# ADC_Buffers.net
KiCad netlist of a schematic drawn in Altium Designer
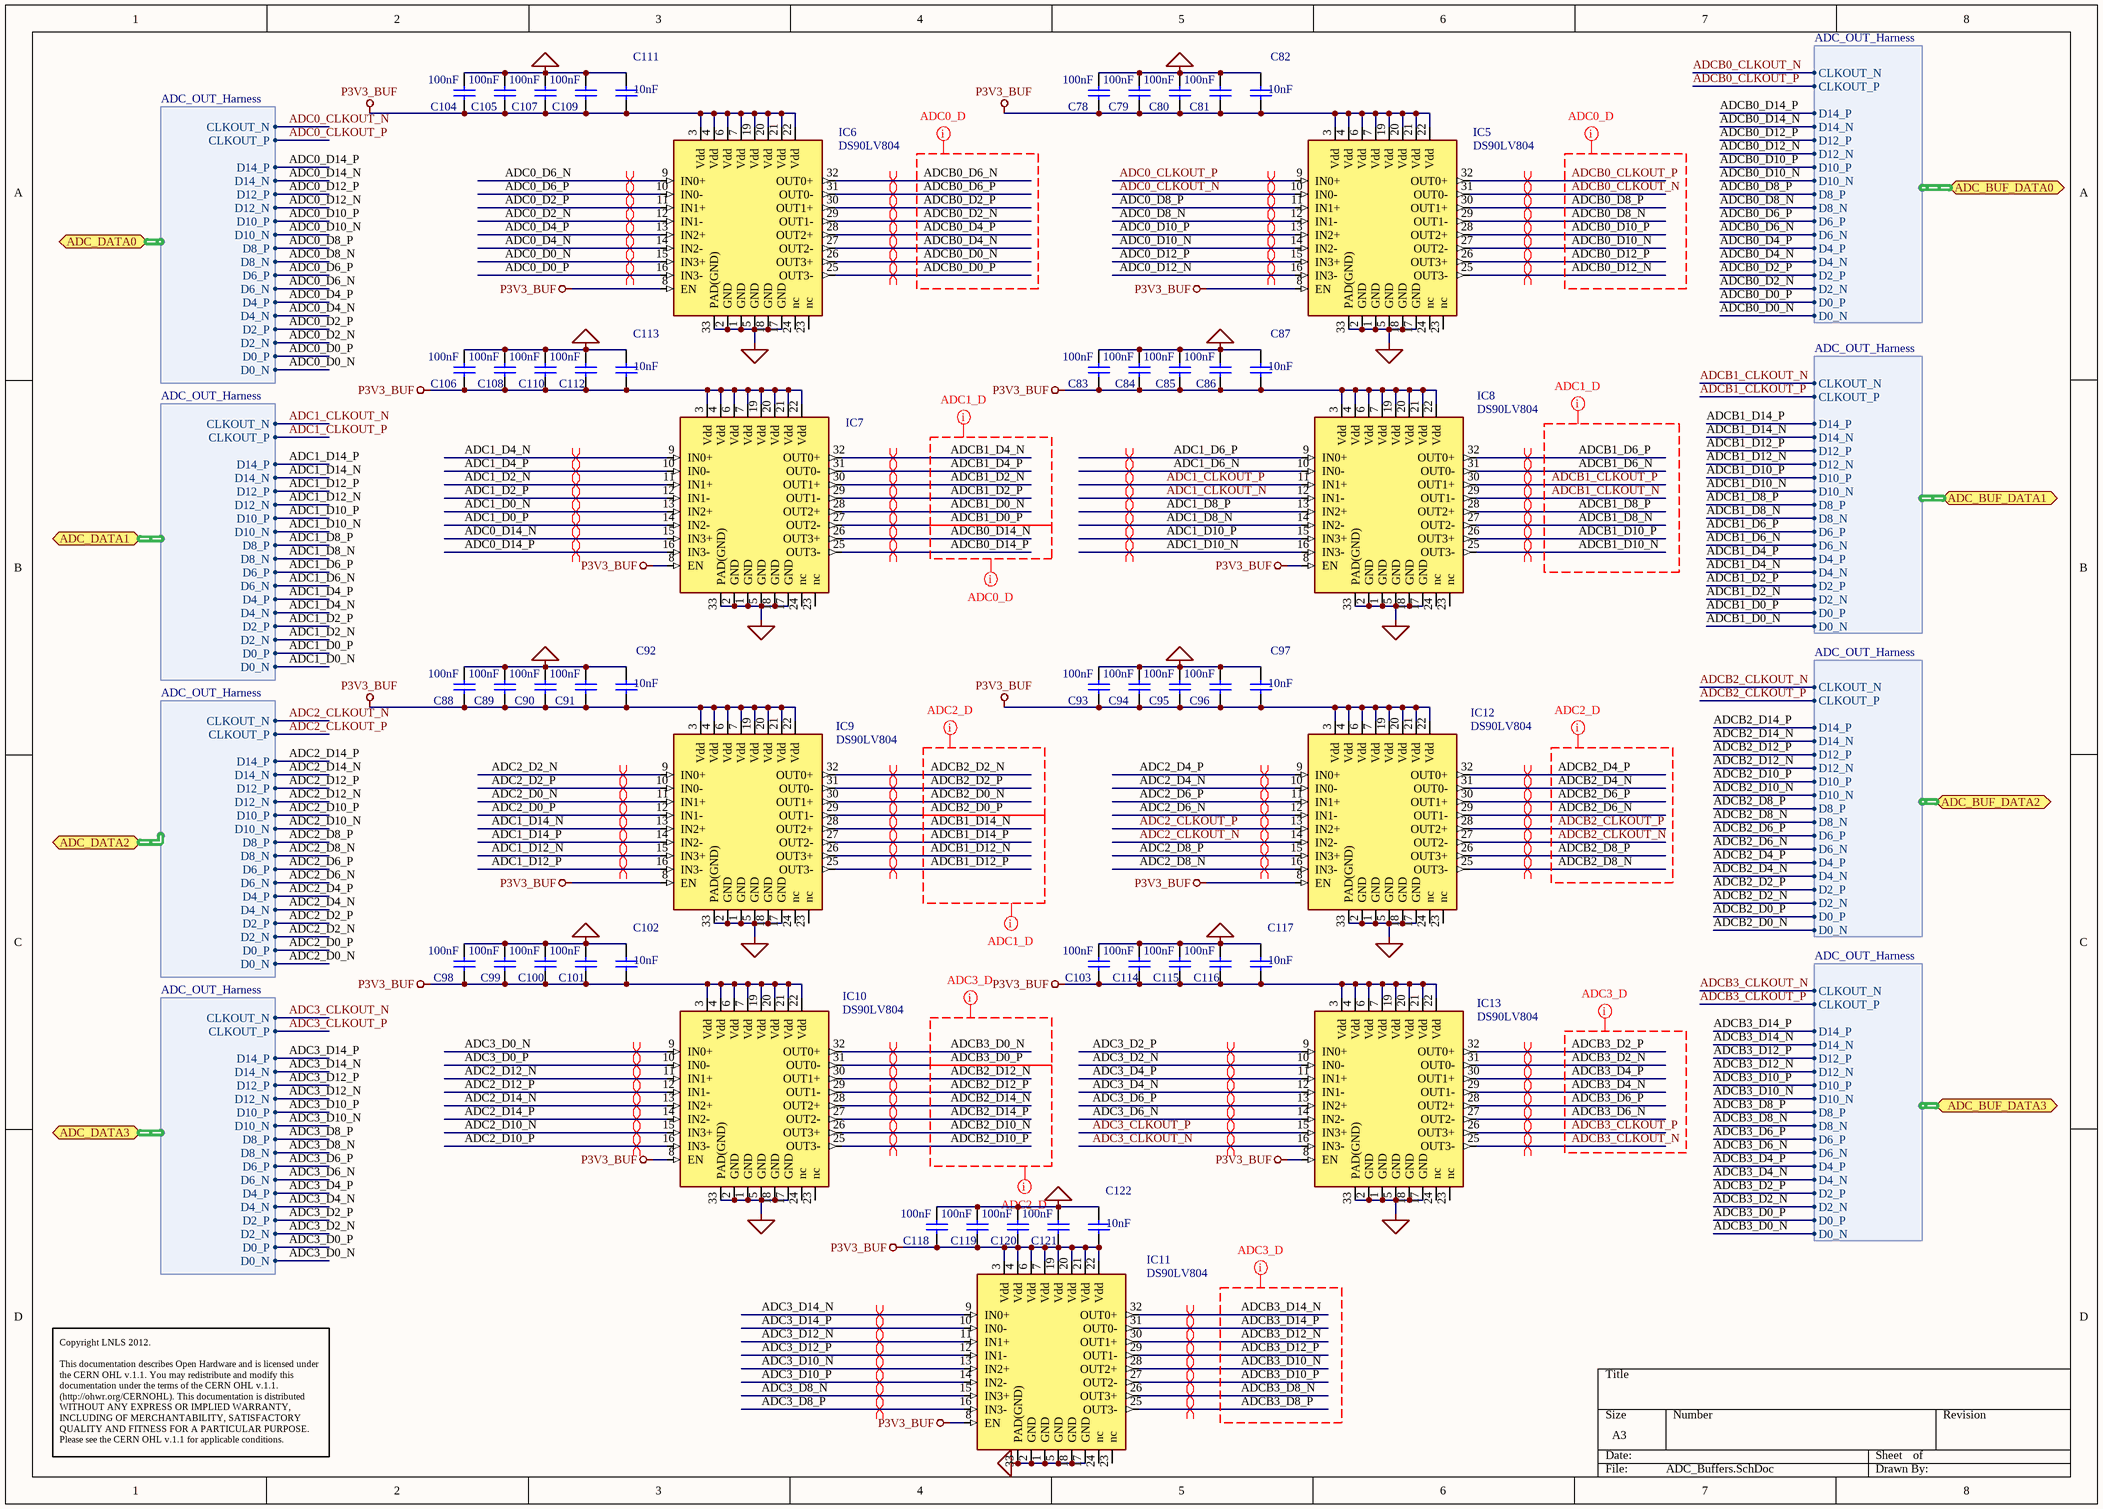
[diagram p0: ADC_Buffers.SchDoc]

(export (version "E")
  (design (tool "Eeschema 10.0.6"))
  (components
    (comp (ref "C78")
      (value "100nF")
      (footprint "CAPC0603X33N")
      (description "Non-polarised capacitor")
      (fields
        (field (name "PART NUMBER") "CC0201_100NF_6.3V_10%_X5R")
        (field (name "VOLTAGE") "6.3V")
        (field (name "AUTHOR") "CERN DEM JLC")
      )
      (libsource (lib "Capacitors") (part "Capacitor - non polarized"))
    )
    (comp (ref "C79")
      (value "100nF")
      (footprint "CAPC0603X33N")
      (description "Non-polarised capacitor")
      (fields
        (field (name "PART NUMBER") "CC0201_100NF_6.3V_10%_X5R")
        (field (name "VOLTAGE") "6.3V")
        (field (name "AUTHOR") "CERN DEM JLC")
      )
      (libsource (lib "Capacitors") (part "Capacitor - non polarized"))
    )
    (comp (ref "C80")
      (value "100nF")
      (footprint "CAPC0603X33N")
      (description "Non-polarised capacitor")
      (fields
        (field (name "PART NUMBER") "CC0201_100NF_6.3V_10%_X5R")
        (field (name "VOLTAGE") "6.3V")
        (field (name "AUTHOR") "CERN DEM JLC")
      )
      (libsource (lib "Capacitors") (part "Capacitor - non polarized"))
    )
    (comp (ref "C81")
      (value "100nF")
      (footprint "CAPC0603X33N")
      (description "Non-polarised capacitor")
      (fields
        (field (name "PART NUMBER") "CC0201_100NF_6.3V_10%_X5R")
        (field (name "VOLTAGE") "6.3V")
        (field (name "AUTHOR") "CERN DEM JLC")
      )
      (libsource (lib "Capacitors") (part "Capacitor - non polarized"))
    )
    (comp (ref "C82")
      (value "10nF")
      (footprint "CAPC0603X33N")
      (description "Non-polarised capacitor")
      (fields
        (field (name "PART NUMBER") "CC0201_10NF_10V_10%_X7R")
        (field (name "VOLTAGE") "10V")
        (field (name "AUTHOR") "LNLS DIG GBMB")
      )
      (libsource (lib "Capacitors") (part "Capacitor - non polarized"))
    )
    (comp (ref "C83")
      (value "100nF")
      (footprint "CAPC0603X33N")
      (description "Non-polarised capacitor")
      (fields
        (field (name "PART NUMBER") "CC0201_100NF_6.3V_10%_X5R")
        (field (name "VOLTAGE") "6.3V")
        (field (name "AUTHOR") "CERN DEM JLC")
      )
      (libsource (lib "Capacitors") (part "Capacitor - non polarized"))
    )
    (comp (ref "C84")
      (value "100nF")
      (footprint "CAPC0603X33N")
      (description "Non-polarised capacitor")
      (fields
        (field (name "PART NUMBER") "CC0201_100NF_6.3V_10%_X5R")
        (field (name "VOLTAGE") "6.3V")
        (field (name "AUTHOR") "CERN DEM JLC")
      )
      (libsource (lib "Capacitors") (part "Capacitor - non polarized"))
    )
    (comp (ref "C85")
      (value "100nF")
      (footprint "CAPC0603X33N")
      (description "Non-polarised capacitor")
      (fields
        (field (name "PART NUMBER") "CC0201_100NF_6.3V_10%_X5R")
        (field (name "VOLTAGE") "6.3V")
        (field (name "AUTHOR") "CERN DEM JLC")
      )
      (libsource (lib "Capacitors") (part "Capacitor - non polarized"))
    )
    (comp (ref "C86")
      (value "100nF")
      (footprint "CAPC0603X33N")
      (description "Non-polarised capacitor")
      (fields
        (field (name "PART NUMBER") "CC0201_100NF_6.3V_10%_X5R")
        (field (name "VOLTAGE") "6.3V")
        (field (name "AUTHOR") "CERN DEM JLC")
      )
      (libsource (lib "Capacitors") (part "Capacitor - non polarized"))
    )
    (comp (ref "C87")
      (value "10nF")
      (footprint "CAPC0603X33N")
      (description "Non-polarised capacitor")
      (fields
        (field (name "PART NUMBER") "CC0201_10NF_10V_10%_X7R")
        (field (name "VOLTAGE") "10V")
        (field (name "AUTHOR") "LNLS DIG GBMB")
      )
      (libsource (lib "Capacitors") (part "Capacitor - non polarized"))
    )
    (comp (ref "C88")
      (value "100nF")
      (footprint "CAPC0603X33N")
      (description "Non-polarised capacitor")
      (fields
        (field (name "PART NUMBER") "CC0201_100NF_6.3V_10%_X5R")
        (field (name "VOLTAGE") "6.3V")
        (field (name "AUTHOR") "CERN DEM JLC")
      )
      (libsource (lib "Capacitors") (part "Capacitor - non polarized"))
    )
    (comp (ref "C89")
      (value "100nF")
      (footprint "CAPC0603X33N")
      (description "Non-polarised capacitor")
      (fields
        (field (name "PART NUMBER") "CC0201_100NF_6.3V_10%_X5R")
        (field (name "VOLTAGE") "6.3V")
        (field (name "AUTHOR") "CERN DEM JLC")
      )
      (libsource (lib "Capacitors") (part "Capacitor - non polarized"))
    )
    (comp (ref "C90")
      (value "100nF")
      (footprint "CAPC0603X33N")
      (description "Non-polarised capacitor")
      (fields
        (field (name "PART NUMBER") "CC0201_100NF_6.3V_10%_X5R")
        (field (name "VOLTAGE") "6.3V")
        (field (name "AUTHOR") "CERN DEM JLC")
      )
      (libsource (lib "Capacitors") (part "Capacitor - non polarized"))
    )
    (comp (ref "C91")
      (value "100nF")
      (footprint "CAPC0603X33N")
      (description "Non-polarised capacitor")
      (fields
        (field (name "PART NUMBER") "CC0201_100NF_6.3V_10%_X5R")
        (field (name "VOLTAGE") "6.3V")
        (field (name "AUTHOR") "CERN DEM JLC")
      )
      (libsource (lib "Capacitors") (part "Capacitor - non polarized"))
    )
    (comp (ref "C92")
      (value "10nF")
      (footprint "CAPC0603X33N")
      (description "Non-polarised capacitor")
      (fields
        (field (name "PART NUMBER") "CC0201_10NF_10V_10%_X7R")
        (field (name "VOLTAGE") "10V")
        (field (name "AUTHOR") "LNLS DIG GBMB")
      )
      (libsource (lib "Capacitors") (part "Capacitor - non polarized"))
    )
    (comp (ref "C93")
      (value "100nF")
      (footprint "CAPC0603X33N")
      (description "Non-polarised capacitor")
      (fields
        (field (name "PART NUMBER") "CC0201_100NF_6.3V_10%_X5R")
        (field (name "VOLTAGE") "6.3V")
        (field (name "AUTHOR") "CERN DEM JLC")
      )
      (libsource (lib "Capacitors") (part "Capacitor - non polarized"))
    )
    (comp (ref "C94")
      (value "100nF")
      (footprint "CAPC0603X33N")
      (description "Non-polarised capacitor")
      (fields
        (field (name "PART NUMBER") "CC0201_100NF_6.3V_10%_X5R")
        (field (name "VOLTAGE") "6.3V")
        (field (name "AUTHOR") "CERN DEM JLC")
      )
      (libsource (lib "Capacitors") (part "Capacitor - non polarized"))
    )
    (comp (ref "C95")
      (value "100nF")
      (footprint "CAPC0603X33N")
      (description "Non-polarised capacitor")
      (fields
        (field (name "PART NUMBER") "CC0201_100NF_6.3V_10%_X5R")
        (field (name "VOLTAGE") "6.3V")
        (field (name "AUTHOR") "CERN DEM JLC")
      )
      (libsource (lib "Capacitors") (part "Capacitor - non polarized"))
    )
    (comp (ref "C96")
      (value "100nF")
      (footprint "CAPC0603X33N")
      (description "Non-polarised capacitor")
      (fields
        (field (name "PART NUMBER") "CC0201_100NF_6.3V_10%_X5R")
        (field (name "VOLTAGE") "6.3V")
        (field (name "AUTHOR") "CERN DEM JLC")
      )
      (libsource (lib "Capacitors") (part "Capacitor - non polarized"))
    )
    (comp (ref "C97")
      (value "10nF")
      (footprint "CAPC0603X33N")
      (description "Non-polarised capacitor")
      (fields
        (field (name "PART NUMBER") "CC0201_10NF_10V_10%_X7R")
        (field (name "VOLTAGE") "10V")
        (field (name "AUTHOR") "LNLS DIG GBMB")
      )
      (libsource (lib "Capacitors") (part "Capacitor - non polarized"))
    )
    (comp (ref "C98")
      (value "100nF")
      (footprint "CAPC0603X33N")
      (description "Non-polarised capacitor")
      (fields
        (field (name "PART NUMBER") "CC0201_100NF_6.3V_10%_X5R")
        (field (name "VOLTAGE") "6.3V")
        (field (name "AUTHOR") "CERN DEM JLC")
      )
      (libsource (lib "Capacitors") (part "Capacitor - non polarized"))
    )
    (comp (ref "C99")
      (value "100nF")
      (footprint "CAPC0603X33N")
      (description "Non-polarised capacitor")
      (fields
        (field (name "PART NUMBER") "CC0201_100NF_6.3V_10%_X5R")
        (field (name "VOLTAGE") "6.3V")
        (field (name "AUTHOR") "CERN DEM JLC")
      )
      (libsource (lib "Capacitors") (part "Capacitor - non polarized"))
    )
    (comp (ref "C100")
      (value "100nF")
      (footprint "CAPC0603X33N")
      (description "Non-polarised capacitor")
      (fields
        (field (name "PART NUMBER") "CC0201_100NF_6.3V_10%_X5R")
        (field (name "VOLTAGE") "6.3V")
        (field (name "AUTHOR") "CERN DEM JLC")
      )
      (libsource (lib "Capacitors") (part "Capacitor - non polarized"))
    )
    (comp (ref "C101")
      (value "100nF")
      (footprint "CAPC0603X33N")
      (description "Non-polarised capacitor")
      (fields
        (field (name "PART NUMBER") "CC0201_100NF_6.3V_10%_X5R")
        (field (name "VOLTAGE") "6.3V")
        (field (name "AUTHOR") "CERN DEM JLC")
      )
      (libsource (lib "Capacitors") (part "Capacitor - non polarized"))
    )
    (comp (ref "C102")
      (value "10nF")
      (footprint "CAPC0603X33N")
      (description "Non-polarised capacitor")
      (fields
        (field (name "PART NUMBER") "CC0201_10NF_10V_10%_X7R")
        (field (name "VOLTAGE") "10V")
        (field (name "AUTHOR") "LNLS DIG GBMB")
      )
      (libsource (lib "Capacitors") (part "Capacitor - non polarized"))
    )
    (comp (ref "C103")
      (value "100nF")
      (footprint "CAPC0603X33N")
      (description "Non-polarised capacitor")
      (fields
        (field (name "PART NUMBER") "CC0201_100NF_6.3V_10%_X5R")
        (field (name "VOLTAGE") "6.3V")
        (field (name "AUTHOR") "CERN DEM JLC")
      )
      (libsource (lib "Capacitors") (part "Capacitor - non polarized"))
    )
    (comp (ref "C104")
      (value "100nF")
      (footprint "CAPC0603X33N")
      (description "Non-polarised capacitor")
      (fields
        (field (name "PART NUMBER") "CC0201_100NF_6.3V_10%_X5R")
        (field (name "VOLTAGE") "6.3V")
        (field (name "AUTHOR") "CERN DEM JLC")
      )
      (libsource (lib "Capacitors") (part "Capacitor - non polarized"))
    )
    (comp (ref "C105")
      (value "100nF")
      (footprint "CAPC0603X33N")
      (description "Non-polarised capacitor")
      (fields
        (field (name "PART NUMBER") "CC0201_100NF_6.3V_10%_X5R")
        (field (name "VOLTAGE") "6.3V")
        (field (name "AUTHOR") "CERN DEM JLC")
      )
      (libsource (lib "Capacitors") (part "Capacitor - non polarized"))
    )
    (comp (ref "C106")
      (value "100nF")
      (footprint "CAPC0603X33N")
      (description "Non-polarised capacitor")
      (fields
        (field (name "PART NUMBER") "CC0201_100NF_6.3V_10%_X5R")
        (field (name "VOLTAGE") "6.3V")
        (field (name "AUTHOR") "CERN DEM JLC")
      )
      (libsource (lib "Capacitors") (part "Capacitor - non polarized"))
    )
    (comp (ref "C107")
      (value "100nF")
      (footprint "CAPC0603X33N")
      (description "Non-polarised capacitor")
      (fields
        (field (name "PART NUMBER") "CC0201_100NF_6.3V_10%_X5R")
        (field (name "VOLTAGE") "6.3V")
        (field (name "AUTHOR") "CERN DEM JLC")
      )
      (libsource (lib "Capacitors") (part "Capacitor - non polarized"))
    )
    (comp (ref "C108")
      (value "100nF")
      (footprint "CAPC0603X33N")
      (description "Non-polarised capacitor")
      (fields
        (field (name "PART NUMBER") "CC0201_100NF_6.3V_10%_X5R")
        (field (name "VOLTAGE") "6.3V")
        (field (name "AUTHOR") "CERN DEM JLC")
      )
      (libsource (lib "Capacitors") (part "Capacitor - non polarized"))
    )
    (comp (ref "C109")
      (value "100nF")
      (footprint "CAPC0603X33N")
      (description "Non-polarised capacitor")
      (fields
        (field (name "PART NUMBER") "CC0201_100NF_6.3V_10%_X5R")
        (field (name "VOLTAGE") "6.3V")
        (field (name "AUTHOR") "CERN DEM JLC")
      )
      (libsource (lib "Capacitors") (part "Capacitor - non polarized"))
    )
    (comp (ref "C110")
      (value "100nF")
      (footprint "CAPC0603X33N")
      (description "Non-polarised capacitor")
      (fields
        (field (name "PART NUMBER") "CC0201_100NF_6.3V_10%_X5R")
        (field (name "VOLTAGE") "6.3V")
        (field (name "AUTHOR") "CERN DEM JLC")
      )
      (libsource (lib "Capacitors") (part "Capacitor - non polarized"))
    )
    (comp (ref "C111")
      (value "10nF")
      (footprint "CAPC0603X33N")
      (description "Non-polarised capacitor")
      (fields
        (field (name "PART NUMBER") "CC0201_10NF_10V_10%_X7R")
        (field (name "VOLTAGE") "10V")
        (field (name "AUTHOR") "LNLS DIG GBMB")
      )
      (libsource (lib "Capacitors") (part "Capacitor - non polarized"))
    )
    (comp (ref "C112")
      (value "100nF")
      (footprint "CAPC0603X33N")
      (description "Non-polarised capacitor")
      (fields
        (field (name "PART NUMBER") "CC0201_100NF_6.3V_10%_X5R")
        (field (name "VOLTAGE") "6.3V")
        (field (name "AUTHOR") "CERN DEM JLC")
      )
      (libsource (lib "Capacitors") (part "Capacitor - non polarized"))
    )
    (comp (ref "C113")
      (value "10nF")
      (footprint "CAPC0603X33N")
      (description "Non-polarised capacitor")
      (fields
        (field (name "PART NUMBER") "CC0201_10NF_10V_10%_X7R")
        (field (name "VOLTAGE") "10V")
        (field (name "AUTHOR") "LNLS DIG GBMB")
      )
      (libsource (lib "Capacitors") (part "Capacitor - non polarized"))
    )
    (comp (ref "C114")
      (value "100nF")
      (footprint "CAPC0603X33N")
      (description "Non-polarised capacitor")
      (fields
        (field (name "PART NUMBER") "CC0201_100NF_6.3V_10%_X5R")
        (field (name "VOLTAGE") "6.3V")
        (field (name "AUTHOR") "CERN DEM JLC")
      )
      (libsource (lib "Capacitors") (part "Capacitor - non polarized"))
    )
    (comp (ref "C115")
      (value "100nF")
      (footprint "CAPC0603X33N")
      (description "Non-polarised capacitor")
      (fields
        (field (name "PART NUMBER") "CC0201_100NF_6.3V_10%_X5R")
        (field (name "VOLTAGE") "6.3V")
        (field (name "AUTHOR") "CERN DEM JLC")
      )
      (libsource (lib "Capacitors") (part "Capacitor - non polarized"))
    )
    (comp (ref "C116")
      (value "100nF")
      (footprint "CAPC0603X33N")
      (description "Non-polarised capacitor")
      (fields
        (field (name "PART NUMBER") "CC0201_100NF_6.3V_10%_X5R")
        (field (name "VOLTAGE") "6.3V")
        (field (name "AUTHOR") "CERN DEM JLC")
      )
      (libsource (lib "Capacitors") (part "Capacitor - non polarized"))
    )
    (comp (ref "C117")
      (value "10nF")
      (footprint "CAPC0603X33N")
      (description "Non-polarised capacitor")
      (fields
        (field (name "PART NUMBER") "CC0201_10NF_10V_10%_X7R")
        (field (name "VOLTAGE") "10V")
        (field (name "AUTHOR") "LNLS DIG GBMB")
      )
      (libsource (lib "Capacitors") (part "Capacitor - non polarized"))
    )
    (comp (ref "C118")
      (value "100nF")
      (footprint "CAPC0603X33N")
      (description "Non-polarised capacitor")
      (fields
        (field (name "PART NUMBER") "CC0201_100NF_6.3V_10%_X5R")
        (field (name "VOLTAGE") "6.3V")
        (field (name "AUTHOR") "CERN DEM JLC")
      )
      (libsource (lib "Capacitors") (part "Capacitor - non polarized"))
    )
    (comp (ref "C119")
      (value "100nF")
      (footprint "CAPC0603X33N")
      (description "Non-polarised capacitor")
      (fields
        (field (name "PART NUMBER") "CC0201_100NF_6.3V_10%_X5R")
        (field (name "VOLTAGE") "6.3V")
        (field (name "AUTHOR") "CERN DEM JLC")
      )
      (libsource (lib "Capacitors") (part "Capacitor - non polarized"))
    )
    (comp (ref "C120")
      (value "100nF")
      (footprint "CAPC0603X33N")
      (description "Non-polarised capacitor")
      (fields
        (field (name "PART NUMBER") "CC0201_100NF_6.3V_10%_X5R")
        (field (name "VOLTAGE") "6.3V")
        (field (name "AUTHOR") "CERN DEM JLC")
      )
      (libsource (lib "Capacitors") (part "Capacitor - non polarized"))
    )
    (comp (ref "C121")
      (value "100nF")
      (footprint "CAPC0603X33N")
      (description "Non-polarised capacitor")
      (fields
        (field (name "PART NUMBER") "CC0201_100NF_6.3V_10%_X5R")
        (field (name "VOLTAGE") "6.3V")
        (field (name "AUTHOR") "CERN DEM JLC")
      )
      (libsource (lib "Capacitors") (part "Capacitor - non polarized"))
    )
    (comp (ref "C122")
      (value "10nF")
      (footprint "CAPC0603X33N")
      (description "Non-polarised capacitor")
      (fields
        (field (name "PART NUMBER") "CC0201_10NF_10V_10%_X7R")
        (field (name "VOLTAGE") "10V")
        (field (name "AUTHOR") "LNLS DIG GBMB")
      )
      (libsource (lib "Capacitors") (part "Capacitor - non polarized"))
    )
    (comp (ref "IC5")
      (value "DS90LV804")
      (footprint "QFN50P500X500X80-33N-S320")
      (description "4-Channel 800 Mbps LVDS Buffer/Repeater")
      (fields
        (field (name "PART NUMBER") "DS90LV804TSQ")
        (field (name "MANUFACTURER") "TEXAS INSTRUMENTS")
        (field (name "AUTHOR") "LNLS DIG GBMB")
      )
      (libsource (lib "ICs And Semiconductors_LNLS") (part "DS90LV804"))
    )
    (comp (ref "IC6")
      (value "DS90LV804")
      (footprint "QFN50P500X500X80-33N-S320")
      (description "4-Channel 800 Mbps LVDS Buffer/Repeater")
      (fields
        (field (name "PART NUMBER") "DS90LV804TSQ")
        (field (name "MANUFACTURER") "TEXAS INSTRUMENTS")
        (field (name "AUTHOR") "LNLS DIG GBMB")
      )
      (libsource (lib "ICs And Semiconductors_LNLS") (part "DS90LV804"))
    )
    (comp (ref "IC7")
      (value "DS90LV804")
      (footprint "QFN50P500X500X80-33N-S320")
      (description "4-Channel 800 Mbps LVDS Buffer/Repeater")
      (fields
        (field (name "PART NUMBER") "DS90LV804TSQ")
        (field (name "MANUFACTURER") "TEXAS INSTRUMENTS")
        (field (name "AUTHOR") "LNLS DIG GBMB")
      )
      (libsource (lib "ICs And Semiconductors_LNLS") (part "DS90LV804"))
    )
    (comp (ref "IC8")
      (value "DS90LV804")
      (footprint "QFN50P500X500X80-33N-S320")
      (description "4-Channel 800 Mbps LVDS Buffer/Repeater")
      (fields
        (field (name "PART NUMBER") "DS90LV804TSQ")
        (field (name "MANUFACTURER") "TEXAS INSTRUMENTS")
        (field (name "AUTHOR") "LNLS DIG GBMB")
      )
      (libsource (lib "ICs And Semiconductors_LNLS") (part "DS90LV804"))
    )
    (comp (ref "IC9")
      (value "DS90LV804")
      (footprint "QFN50P500X500X80-33N-S320")
      (description "4-Channel 800 Mbps LVDS Buffer/Repeater")
      (fields
        (field (name "PART NUMBER") "DS90LV804TSQ")
        (field (name "MANUFACTURER") "TEXAS INSTRUMENTS")
        (field (name "AUTHOR") "LNLS DIG GBMB")
      )
      (libsource (lib "ICs And Semiconductors_LNLS") (part "DS90LV804"))
    )
    (comp (ref "IC10")
      (value "DS90LV804")
      (footprint "QFN50P500X500X80-33N-S320")
      (description "4-Channel 800 Mbps LVDS Buffer/Repeater")
      (fields
        (field (name "PART NUMBER") "DS90LV804TSQ")
        (field (name "MANUFACTURER") "TEXAS INSTRUMENTS")
        (field (name "AUTHOR") "LNLS DIG GBMB")
      )
      (libsource (lib "ICs And Semiconductors_LNLS") (part "DS90LV804"))
    )
    (comp (ref "IC11")
      (value "DS90LV804")
      (footprint "QFN50P500X500X80-33N-S320")
      (description "4-Channel 800 Mbps LVDS Buffer/Repeater")
      (fields
        (field (name "PART NUMBER") "DS90LV804TSQ")
        (field (name "MANUFACTURER") "TEXAS INSTRUMENTS")
        (field (name "AUTHOR") "LNLS DIG GBMB")
      )
      (libsource (lib "ICs And Semiconductors_LNLS") (part "DS90LV804"))
    )
    (comp (ref "IC12")
      (value "DS90LV804")
      (footprint "QFN50P500X500X80-33N-S320")
      (description "4-Channel 800 Mbps LVDS Buffer/Repeater")
      (fields
        (field (name "PART NUMBER") "DS90LV804TSQ")
        (field (name "MANUFACTURER") "TEXAS INSTRUMENTS")
        (field (name "AUTHOR") "LNLS DIG GBMB")
      )
      (libsource (lib "ICs And Semiconductors_LNLS") (part "DS90LV804"))
    )
    (comp (ref "IC13")
      (value "DS90LV804")
      (footprint "QFN50P500X500X80-33N-S320")
      (description "4-Channel 800 Mbps LVDS Buffer/Repeater")
      (fields
        (field (name "PART NUMBER") "DS90LV804TSQ")
        (field (name "MANUFACTURER") "TEXAS INSTRUMENTS")
        (field (name "AUTHOR") "LNLS DIG GBMB")
      )
      (libsource (lib "ICs And Semiconductors_LNLS") (part "DS90LV804"))
    )
  )
  (nets
    (net (code "2") (name "/ADC0_CLKOUT_N") (class "Default")
      (node (ref "IC5") (pin "10") (pinfunction "IN0-_10") (pintype "input"))
    )
    (net (code "3") (name "/ADC0_CLKOUT_P") (class "Default")
      (node (ref "IC5") (pin "9") (pinfunction "IN0+_9") (pintype "input"))
    )
    (net (code "4") (name "/ADC0_D0_N") (class "Default")
      (node (ref "IC6") (pin "15") (pinfunction "IN3+_15") (pintype "input"))
    )
    (net (code "5") (name "/ADC0_D0_P") (class "Default")
      (node (ref "IC6") (pin "16") (pinfunction "IN3-_16") (pintype "input"))
    )
    (net (code "6") (name "/ADC0_D2_N") (class "Default")
      (node (ref "IC6") (pin "12") (pinfunction "IN1-_12") (pintype "input"))
    )
    (net (code "7") (name "/ADC0_D2_P") (class "Default")
      (node (ref "IC6") (pin "11") (pinfunction "IN1+_11") (pintype "input"))
    )
    (net (code "8") (name "/ADC0_D4_N") (class "Default")
      (node (ref "IC6") (pin "14") (pinfunction "IN2-_14") (pintype "input"))
    )
    (net (code "9") (name "/ADC0_D4_P") (class "Default")
      (node (ref "IC6") (pin "13") (pinfunction "IN2+_13") (pintype "input"))
    )
    (net (code "10") (name "/ADC0_D6_N") (class "Default")
      (node (ref "IC6") (pin "9") (pinfunction "IN0+_9") (pintype "input"))
    )
    (net (code "11") (name "/ADC0_D6_P") (class "Default")
      (node (ref "IC6") (pin "10") (pinfunction "IN0-_10") (pintype "input"))
    )
    (net (code "12") (name "/ADC0_D8_N") (class "Default")
      (node (ref "IC5") (pin "12") (pinfunction "IN1-_12") (pintype "input"))
    )
    (net (code "13") (name "/ADC0_D8_P") (class "Default")
      (node (ref "IC5") (pin "11") (pinfunction "IN1+_11") (pintype "input"))
    )
    (net (code "14") (name "/ADC0_D10_N") (class "Default")
      (node (ref "IC5") (pin "14") (pinfunction "IN2-_14") (pintype "input"))
    )
    (net (code "15") (name "/ADC0_D10_P") (class "Default")
      (node (ref "IC5") (pin "13") (pinfunction "IN2+_13") (pintype "input"))
    )
    (net (code "16") (name "/ADC0_D12_N") (class "Default")
      (node (ref "IC5") (pin "16") (pinfunction "IN3-_16") (pintype "input"))
    )
    (net (code "17") (name "/ADC0_D12_P") (class "Default")
      (node (ref "IC5") (pin "15") (pinfunction "IN3+_15") (pintype "input"))
    )
    (net (code "18") (name "/ADC0_D14_N") (class "Default")
      (node (ref "IC7") (pin "15") (pinfunction "IN3+_15") (pintype "input"))
    )
    (net (code "19") (name "/ADC0_D14_P") (class "Default")
      (node (ref "IC7") (pin "16") (pinfunction "IN3-_16") (pintype "input"))
    )
    (net (code "20") (name "/ADC1_CLKOUT_N") (class "Default")
      (node (ref "IC8") (pin "12") (pinfunction "IN1-_12") (pintype "input"))
    )
    (net (code "21") (name "/ADC1_CLKOUT_P") (class "Default")
      (node (ref "IC8") (pin "11") (pinfunction "IN1+_11") (pintype "input"))
    )
    (net (code "22") (name "/ADC1_D0_N") (class "Default")
      (node (ref "IC7") (pin "13") (pinfunction "IN2+_13") (pintype "input"))
    )
    (net (code "23") (name "/ADC1_D0_P") (class "Default")
      (node (ref "IC7") (pin "14") (pinfunction "IN2-_14") (pintype "input"))
    )
    (net (code "24") (name "/ADC1_D2_N") (class "Default")
      (node (ref "IC7") (pin "11") (pinfunction "IN1+_11") (pintype "input"))
    )
    (net (code "25") (name "/ADC1_D2_P") (class "Default")
      (node (ref "IC7") (pin "12") (pinfunction "IN1-_12") (pintype "input"))
    )
    (net (code "26") (name "/ADC1_D4_N") (class "Default")
      (node (ref "IC7") (pin "9") (pinfunction "IN0+_9") (pintype "input"))
    )
    (net (code "27") (name "/ADC1_D4_P") (class "Default")
      (node (ref "IC7") (pin "10") (pinfunction "IN0-_10") (pintype "input"))
    )
    (net (code "28") (name "/ADC1_D6_N") (class "Default")
      (node (ref "IC8") (pin "10") (pinfunction "IN0-_10") (pintype "input"))
    )
    (net (code "29") (name "/ADC1_D6_P") (class "Default")
      (node (ref "IC8") (pin "9") (pinfunction "IN0+_9") (pintype "input"))
    )
    (net (code "30") (name "/ADC1_D8_N") (class "Default")
      (node (ref "IC8") (pin "14") (pinfunction "IN2-_14") (pintype "input"))
    )
    (net (code "31") (name "/ADC1_D8_P") (class "Default")
      (node (ref "IC8") (pin "13") (pinfunction "IN2+_13") (pintype "input"))
    )
    (net (code "32") (name "/ADC1_D10_N") (class "Default")
      (node (ref "IC8") (pin "16") (pinfunction "IN3-_16") (pintype "input"))
    )
    (net (code "33") (name "/ADC1_D10_P") (class "Default")
      (node (ref "IC8") (pin "15") (pinfunction "IN3+_15") (pintype "input"))
    )
    (net (code "34") (name "/ADC1_D12_N") (class "Default")
      (node (ref "IC9") (pin "15") (pinfunction "IN3+_15") (pintype "input"))
    )
    (net (code "35") (name "/ADC1_D12_P") (class "Default")
      (node (ref "IC9") (pin "16") (pinfunction "IN3-_16") (pintype "input"))
    )
    (net (code "36") (name "/ADC1_D14_N") (class "Default")
      (node (ref "IC9") (pin "13") (pinfunction "IN2+_13") (pintype "input"))
    )
    (net (code "37") (name "/ADC1_D14_P") (class "Default")
      (node (ref "IC9") (pin "14") (pinfunction "IN2-_14") (pintype "input"))
    )
    (net (code "38") (name "/ADC2_CLKOUT_N") (class "Default")
      (node (ref "IC12") (pin "14") (pinfunction "IN2-_14") (pintype "input"))
    )
    (net (code "39") (name "/ADC2_CLKOUT_P") (class "Default")
      (node (ref "IC12") (pin "13") (pinfunction "IN2+_13") (pintype "input"))
    )
    (net (code "40") (name "/ADC2_D0_N") (class "Default")
      (node (ref "IC9") (pin "11") (pinfunction "IN1+_11") (pintype "input"))
    )
    (net (code "41") (name "/ADC2_D0_P") (class "Default")
      (node (ref "IC9") (pin "12") (pinfunction "IN1-_12") (pintype "input"))
    )
    (net (code "42") (name "/ADC2_D2_N") (class "Default")
      (node (ref "IC9") (pin "9") (pinfunction "IN0+_9") (pintype "input"))
    )
    (net (code "43") (name "/ADC2_D2_P") (class "Default")
      (node (ref "IC9") (pin "10") (pinfunction "IN0-_10") (pintype "input"))
    )
    (net (code "44") (name "/ADC2_D4_N") (class "Default")
      (node (ref "IC12") (pin "10") (pinfunction "IN0-_10") (pintype "input"))
    )
    (net (code "45") (name "/ADC2_D4_P") (class "Default")
      (node (ref "IC12") (pin "9") (pinfunction "IN0+_9") (pintype "input"))
    )
    (net (code "46") (name "/ADC2_D6_N") (class "Default")
      (node (ref "IC12") (pin "12") (pinfunction "IN1-_12") (pintype "input"))
    )
    (net (code "47") (name "/ADC2_D6_P") (class "Default")
      (node (ref "IC12") (pin "11") (pinfunction "IN1+_11") (pintype "input"))
    )
    (net (code "48") (name "/ADC2_D8_N") (class "Default")
      (node (ref "IC12") (pin "16") (pinfunction "IN3-_16") (pintype "input"))
    )
    (net (code "49") (name "/ADC2_D8_P") (class "Default")
      (node (ref "IC12") (pin "15") (pinfunction "IN3+_15") (pintype "input"))
    )
    (net (code "50") (name "/ADC2_D10_N") (class "Default")
      (node (ref "IC10") (pin "15") (pinfunction "IN3+_15") (pintype "input"))
    )
    (net (code "51") (name "/ADC2_D10_P") (class "Default")
      (node (ref "IC10") (pin "16") (pinfunction "IN3-_16") (pintype "input"))
    )
    (net (code "52") (name "/ADC2_D12_N") (class "Default")
      (node (ref "IC10") (pin "11") (pinfunction "IN1+_11") (pintype "input"))
    )
    (net (code "53") (name "/ADC2_D12_P") (class "Default")
      (node (ref "IC10") (pin "12") (pinfunction "IN1-_12") (pintype "input"))
    )
    (net (code "54") (name "/ADC2_D14_N") (class "Default")
      (node (ref "IC10") (pin "13") (pinfunction "IN2+_13") (pintype "input"))
    )
    (net (code "55") (name "/ADC2_D14_P") (class "Default")
      (node (ref "IC10") (pin "14") (pinfunction "IN2-_14") (pintype "input"))
    )
    (net (code "56") (name "/ADC3_CLKOUT_N") (class "Default")
      (node (ref "IC13") (pin "16") (pinfunction "IN3-_16") (pintype "input"))
    )
    (net (code "57") (name "/ADC3_CLKOUT_P") (class "Default")
      (node (ref "IC13") (pin "15") (pinfunction "IN3+_15") (pintype "input"))
    )
    (net (code "58") (name "/ADC3_D0_N") (class "Default")
      (node (ref "IC10") (pin "9") (pinfunction "IN0+_9") (pintype "input"))
    )
    (net (code "59") (name "/ADC3_D0_P") (class "Default")
      (node (ref "IC10") (pin "10") (pinfunction "IN0-_10") (pintype "input"))
    )
    (net (code "60") (name "/ADC3_D2_N") (class "Default")
      (node (ref "IC13") (pin "10") (pinfunction "IN0-_10") (pintype "input"))
    )
    (net (code "61") (name "/ADC3_D2_P") (class "Default")
      (node (ref "IC13") (pin "9") (pinfunction "IN0+_9") (pintype "input"))
    )
    (net (code "62") (name "/ADC3_D4_N") (class "Default")
      (node (ref "IC13") (pin "12") (pinfunction "IN1-_12") (pintype "input"))
    )
    (net (code "63") (name "/ADC3_D4_P") (class "Default")
      (node (ref "IC13") (pin "11") (pinfunction "IN1+_11") (pintype "input"))
    )
    (net (code "64") (name "/ADC3_D6_N") (class "Default")
      (node (ref "IC13") (pin "14") (pinfunction "IN2-_14") (pintype "input"))
    )
    (net (code "65") (name "/ADC3_D6_P") (class "Default")
      (node (ref "IC13") (pin "13") (pinfunction "IN2+_13") (pintype "input"))
    )
    (net (code "66") (name "/ADC3_D8_N") (class "Default")
      (node (ref "IC11") (pin "15") (pinfunction "IN3+_15") (pintype "input"))
    )
    (net (code "67") (name "/ADC3_D8_P") (class "Default")
      (node (ref "IC11") (pin "16") (pinfunction "IN3-_16") (pintype "input"))
    )
    (net (code "68") (name "/ADC3_D10_N") (class "Default")
      (node (ref "IC11") (pin "13") (pinfunction "IN2+_13") (pintype "input"))
    )
    (net (code "69") (name "/ADC3_D10_P") (class "Default")
      (node (ref "IC11") (pin "14") (pinfunction "IN2-_14") (pintype "input"))
    )
    (net (code "70") (name "/ADC3_D12_N") (class "Default")
      (node (ref "IC11") (pin "11") (pinfunction "IN1+_11") (pintype "input"))
    )
    (net (code "71") (name "/ADC3_D12_P") (class "Default")
      (node (ref "IC11") (pin "12") (pinfunction "IN1-_12") (pintype "input"))
    )
    (net (code "72") (name "/ADC3_D14_N") (class "Default")
      (node (ref "IC11") (pin "9") (pinfunction "IN0+_9") (pintype "input"))
    )
    (net (code "73") (name "/ADC3_D14_P") (class "Default")
      (node (ref "IC11") (pin "10") (pinfunction "IN0-_10") (pintype "input"))
    )
    (net (code "74") (name "/ADCB0_CLKOUT_N") (class "Default")
      (node (ref "IC5") (pin "31") (pinfunction "OUT0-_31") (pintype "output"))
    )
    (net (code "75") (name "/ADCB0_CLKOUT_P") (class "Default")
      (node (ref "IC5") (pin "32") (pinfunction "OUT0+_32") (pintype "output"))
    )
    (net (code "76") (name "/ADCB0_D0_N") (class "Default")
      (node (ref "IC6") (pin "26") (pinfunction "OUT3+_26") (pintype "output"))
    )
    (net (code "77") (name "/ADCB0_D0_P") (class "Default")
      (node (ref "IC6") (pin "25") (pinfunction "OUT3-_25") (pintype "output"))
    )
    (net (code "78") (name "/ADCB0_D2_N") (class "Default")
      (node (ref "IC6") (pin "29") (pinfunction "OUT1-_29") (pintype "output"))
    )
    (net (code "79") (name "/ADCB0_D2_P") (class "Default")
      (node (ref "IC6") (pin "30") (pinfunction "OUT1+_30") (pintype "output"))
    )
    (net (code "80") (name "/ADCB0_D4_N") (class "Default")
      (node (ref "IC6") (pin "27") (pinfunction "OUT2-_27") (pintype "output"))
    )
    (net (code "81") (name "/ADCB0_D4_P") (class "Default")
      (node (ref "IC6") (pin "28") (pinfunction "OUT2+_28") (pintype "output"))
    )
    (net (code "82") (name "/ADCB0_D6_N") (class "Default")
      (node (ref "IC6") (pin "32") (pinfunction "OUT0+_32") (pintype "output"))
    )
    (net (code "83") (name "/ADCB0_D6_P") (class "Default")
      (node (ref "IC6") (pin "31") (pinfunction "OUT0-_31") (pintype "output"))
    )
    (net (code "84") (name "/ADCB0_D8_N") (class "Default")
      (node (ref "IC5") (pin "29") (pinfunction "OUT1-_29") (pintype "output"))
    )
    (net (code "85") (name "/ADCB0_D8_P") (class "Default")
      (node (ref "IC5") (pin "30") (pinfunction "OUT1+_30") (pintype "output"))
    )
    (net (code "86") (name "/ADCB0_D10_N") (class "Default")
      (node (ref "IC5") (pin "27") (pinfunction "OUT2-_27") (pintype "output"))
    )
    (net (code "87") (name "/ADCB0_D10_P") (class "Default")
      (node (ref "IC5") (pin "28") (pinfunction "OUT2+_28") (pintype "output"))
    )
    (net (code "88") (name "/ADCB0_D12_N") (class "Default")
      (node (ref "IC5") (pin "25") (pinfunction "OUT3-_25") (pintype "output"))
    )
    (net (code "89") (name "/ADCB0_D12_P") (class "Default")
      (node (ref "IC5") (pin "26") (pinfunction "OUT3+_26") (pintype "output"))
    )
    (net (code "90") (name "/ADCB0_D14_N") (class "Default")
      (node (ref "IC7") (pin "26") (pinfunction "OUT3+_26") (pintype "output"))
    )
    (net (code "91") (name "/ADCB0_D14_P") (class "Default")
      (node (ref "IC7") (pin "25") (pinfunction "OUT3-_25") (pintype "output"))
    )
    (net (code "92") (name "/ADCB1_CLKOUT_N") (class "Default")
      (node (ref "IC8") (pin "29") (pinfunction "OUT1-_29") (pintype "output"))
    )
    (net (code "93") (name "/ADCB1_CLKOUT_P") (class "Default")
      (node (ref "IC8") (pin "30") (pinfunction "OUT1+_30") (pintype "output"))
    )
    (net (code "94") (name "/ADCB1_D0_N") (class "Default")
      (node (ref "IC7") (pin "28") (pinfunction "OUT2+_28") (pintype "output"))
    )
    (net (code "95") (name "/ADCB1_D0_P") (class "Default")
      (node (ref "IC7") (pin "27") (pinfunction "OUT2-_27") (pintype "output"))
    )
    (net (code "96") (name "/ADCB1_D2_N") (class "Default")
      (node (ref "IC7") (pin "30") (pinfunction "OUT1+_30") (pintype "output"))
    )
    (net (code "97") (name "/ADCB1_D2_P") (class "Default")
      (node (ref "IC7") (pin "29") (pinfunction "OUT1-_29") (pintype "output"))
    )
    (net (code "98") (name "/ADCB1_D4_N") (class "Default")
      (node (ref "IC7") (pin "32") (pinfunction "OUT0+_32") (pintype "output"))
    )
    (net (code "99") (name "/ADCB1_D4_P") (class "Default")
      (node (ref "IC7") (pin "31") (pinfunction "OUT0-_31") (pintype "output"))
    )
    (net (code "100") (name "/ADCB1_D6_N") (class "Default")
      (node (ref "IC8") (pin "31") (pinfunction "OUT0-_31") (pintype "output"))
    )
    (net (code "101") (name "/ADCB1_D6_P") (class "Default")
      (node (ref "IC8") (pin "32") (pinfunction "OUT0+_32") (pintype "output"))
    )
    (net (code "102") (name "/ADCB1_D8_N") (class "Default")
      (node (ref "IC8") (pin "27") (pinfunction "OUT2-_27") (pintype "output"))
    )
    (net (code "103") (name "/ADCB1_D8_P") (class "Default")
      (node (ref "IC8") (pin "28") (pinfunction "OUT2+_28") (pintype "output"))
    )
    (net (code "104") (name "/ADCB1_D10_N") (class "Default")
      (node (ref "IC8") (pin "25") (pinfunction "OUT3-_25") (pintype "output"))
    )
    (net (code "105") (name "/ADCB1_D10_P") (class "Default")
      (node (ref "IC8") (pin "26") (pinfunction "OUT3+_26") (pintype "output"))
    )
    (net (code "106") (name "/ADCB1_D12_N") (class "Default")
      (node (ref "IC9") (pin "26") (pinfunction "OUT3+_26") (pintype "output"))
    )
    (net (code "107") (name "/ADCB1_D12_P") (class "Default")
      (node (ref "IC9") (pin "25") (pinfunction "OUT3-_25") (pintype "output"))
    )
    (net (code "108") (name "/ADCB1_D14_N") (class "Default")
      (node (ref "IC9") (pin "28") (pinfunction "OUT2+_28") (pintype "output"))
    )
    (net (code "109") (name "/ADCB1_D14_P") (class "Default")
      (node (ref "IC9") (pin "27") (pinfunction "OUT2-_27") (pintype "output"))
    )
    (net (code "110") (name "/ADCB2_CLKOUT_N") (class "Default")
      (node (ref "IC12") (pin "27") (pinfunction "OUT2-_27") (pintype "output"))
    )
    (net (code "111") (name "/ADCB2_CLKOUT_P") (class "Default")
      (node (ref "IC12") (pin "28") (pinfunction "OUT2+_28") (pintype "output"))
    )
    (net (code "112") (name "/ADCB2_D0_N") (class "Default")
      (node (ref "IC9") (pin "30") (pinfunction "OUT1+_30") (pintype "output"))
    )
    (net (code "113") (name "/ADCB2_D0_P") (class "Default")
      (node (ref "IC9") (pin "29") (pinfunction "OUT1-_29") (pintype "output"))
    )
    (net (code "114") (name "/ADCB2_D2_N") (class "Default")
      (node (ref "IC9") (pin "32") (pinfunction "OUT0+_32") (pintype "output"))
    )
    (net (code "115") (name "/ADCB2_D2_P") (class "Default")
      (node (ref "IC9") (pin "31") (pinfunction "OUT0-_31") (pintype "output"))
    )
    (net (code "116") (name "/ADCB2_D4_N") (class "Default")
      (node (ref "IC12") (pin "31") (pinfunction "OUT0-_31") (pintype "output"))
    )
    (net (code "117") (name "/ADCB2_D4_P") (class "Default")
      (node (ref "IC12") (pin "32") (pinfunction "OUT0+_32") (pintype "output"))
    )
    (net (code "118") (name "/ADCB2_D6_N") (class "Default")
      (node (ref "IC12") (pin "29") (pinfunction "OUT1-_29") (pintype "output"))
    )
    (net (code "119") (name "/ADCB2_D6_P") (class "Default")
      (node (ref "IC12") (pin "30") (pinfunction "OUT1+_30") (pintype "output"))
    )
    (net (code "120") (name "/ADCB2_D8_N") (class "Default")
      (node (ref "IC12") (pin "25") (pinfunction "OUT3-_25") (pintype "output"))
    )
    (net (code "121") (name "/ADCB2_D8_P") (class "Default")
      (node (ref "IC12") (pin "26") (pinfunction "OUT3+_26") (pintype "output"))
    )
    (net (code "122") (name "/ADCB2_D10_N") (class "Default")
      (node (ref "IC10") (pin "26") (pinfunction "OUT3+_26") (pintype "output"))
    )
    (net (code "123") (name "/ADCB2_D10_P") (class "Default")
      (node (ref "IC10") (pin "25") (pinfunction "OUT3-_25") (pintype "output"))
    )
    (net (code "124") (name "/ADCB2_D12_N") (class "Default")
      (node (ref "IC10") (pin "30") (pinfunction "OUT1+_30") (pintype "output"))
    )
    (net (code "125") (name "/ADCB2_D12_P") (class "Default")
      (node (ref "IC10") (pin "29") (pinfunction "OUT1-_29") (pintype "output"))
    )
    (net (code "126") (name "/ADCB2_D14_N") (class "Default")
      (node (ref "IC10") (pin "28") (pinfunction "OUT2+_28") (pintype "output"))
    )
    (net (code "127") (name "/ADCB2_D14_P") (class "Default")
      (node (ref "IC10") (pin "27") (pinfunction "OUT2-_27") (pintype "output"))
    )
    (net (code "128") (name "/ADCB3_CLKOUT_N") (class "Default")
      (node (ref "IC13") (pin "25") (pinfunction "OUT3-_25") (pintype "output"))
    )
    (net (code "129") (name "/ADCB3_CLKOUT_P") (class "Default")
      (node (ref "IC13") (pin "26") (pinfunction "OUT3+_26") (pintype "output"))
    )
    (net (code "130") (name "/ADCB3_D0_N") (class "Default")
      (node (ref "IC10") (pin "32") (pinfunction "OUT0+_32") (pintype "output"))
    )
    (net (code "131") (name "/ADCB3_D0_P") (class "Default")
      (node (ref "IC10") (pin "31") (pinfunction "OUT0-_31") (pintype "output"))
    )
    (net (code "132") (name "/ADCB3_D2_N") (class "Default")
      (node (ref "IC13") (pin "31") (pinfunction "OUT0-_31") (pintype "output"))
    )
    (net (code "133") (name "/ADCB3_D2_P") (class "Default")
      (node (ref "IC13") (pin "32") (pinfunction "OUT0+_32") (pintype "output"))
    )
    (net (code "134") (name "/ADCB3_D4_N") (class "Default")
      (node (ref "IC13") (pin "29") (pinfunction "OUT1-_29") (pintype "output"))
    )
    (net (code "135") (name "/ADCB3_D4_P") (class "Default")
      (node (ref "IC13") (pin "30") (pinfunction "OUT1+_30") (pintype "output"))
    )
    (net (code "136") (name "/ADCB3_D6_N") (class "Default")
      (node (ref "IC13") (pin "27") (pinfunction "OUT2-_27") (pintype "output"))
    )
    (net (code "137") (name "/ADCB3_D6_P") (class "Default")
      (node (ref "IC13") (pin "28") (pinfunction "OUT2+_28") (pintype "output"))
    )
    (net (code "138") (name "/ADCB3_D8_N") (class "Default")
      (node (ref "IC11") (pin "26") (pinfunction "OUT3+_26") (pintype "output"))
    )
    (net (code "139") (name "/ADCB3_D8_P") (class "Default")
      (node (ref "IC11") (pin "25") (pinfunction "OUT3-_25") (pintype "output"))
    )
    (net (code "140") (name "/ADCB3_D10_N") (class "Default")
      (node (ref "IC11") (pin "28") (pinfunction "OUT2+_28") (pintype "output"))
    )
    (net (code "141") (name "/ADCB3_D10_P") (class "Default")
      (node (ref "IC11") (pin "27") (pinfunction "OUT2-_27") (pintype "output"))
    )
    (net (code "142") (name "/ADCB3_D12_N") (class "Default")
      (node (ref "IC11") (pin "30") (pinfunction "OUT1+_30") (pintype "output"))
    )
    (net (code "143") (name "/ADCB3_D12_P") (class "Default")
      (node (ref "IC11") (pin "29") (pinfunction "OUT1-_29") (pintype "output"))
    )
    (net (code "144") (name "/ADCB3_D14_N") (class "Default")
      (node (ref "IC11") (pin "32") (pinfunction "OUT0+_32") (pintype "output"))
    )
    (net (code "145") (name "/ADCB3_D14_P") (class "Default")
      (node (ref "IC11") (pin "31") (pinfunction "OUT0-_31") (pintype "output"))
    )
    (net (code "147") (name "GND") (class "Default")
      (node (ref "C100") (pin "1") (pinfunction "1_1") (pintype "passive"))
      (node (ref "C101") (pin "1") (pinfunction "1_1") (pintype "passive"))
      (node (ref "C102") (pin "1") (pinfunction "1_1") (pintype "passive"))
      (node (ref "C103") (pin "1") (pinfunction "1_1") (pintype "passive"))
      (node (ref "C104") (pin "1") (pinfunction "1_1") (pintype "passive"))
      (node (ref "C105") (pin "1") (pinfunction "1_1") (pintype "passive"))
      (node (ref "C106") (pin "1") (pinfunction "1_1") (pintype "passive"))
      (node (ref "C107") (pin "1") (pinfunction "1_1") (pintype "passive"))
      (node (ref "C108") (pin "1") (pinfunction "1_1") (pintype "passive"))
      (node (ref "C109") (pin "1") (pinfunction "1_1") (pintype "passive"))
      (node (ref "C110") (pin "1") (pinfunction "1_1") (pintype "passive"))
      (node (ref "C111") (pin "1") (pinfunction "1_1") (pintype "passive"))
      (node (ref "C112") (pin "1") (pinfunction "1_1") (pintype "passive"))
      (node (ref "C113") (pin "1") (pinfunction "1_1") (pintype "passive"))
      (node (ref "C114") (pin "1") (pinfunction "1_1") (pintype "passive"))
      (node (ref "C115") (pin "1") (pinfunction "1_1") (pintype "passive"))
      (node (ref "C116") (pin "1") (pinfunction "1_1") (pintype "passive"))
      (node (ref "C117") (pin "1") (pinfunction "1_1") (pintype "passive"))
      (node (ref "C118") (pin "1") (pinfunction "1_1") (pintype "passive"))
      (node (ref "C119") (pin "1") (pinfunction "1_1") (pintype "passive"))
      (node (ref "C120") (pin "1") (pinfunction "1_1") (pintype "passive"))
      (node (ref "C121") (pin "1") (pinfunction "1_1") (pintype "passive"))
      (node (ref "C122") (pin "1") (pinfunction "1_1") (pintype "passive"))
      (node (ref "C78") (pin "1") (pinfunction "1_1") (pintype "passive"))
      (node (ref "C79") (pin "1") (pinfunction "1_1") (pintype "passive"))
      (node (ref "C80") (pin "1") (pinfunction "1_1") (pintype "passive"))
      (node (ref "C81") (pin "1") (pinfunction "1_1") (pintype "passive"))
      (node (ref "C82") (pin "1") (pinfunction "1_1") (pintype "passive"))
      (node (ref "C83") (pin "1") (pinfunction "1_1") (pintype "passive"))
      (node (ref "C84") (pin "1") (pinfunction "1_1") (pintype "passive"))
      (node (ref "C85") (pin "1") (pinfunction "1_1") (pintype "passive"))
      (node (ref "C86") (pin "1") (pinfunction "1_1") (pintype "passive"))
      (node (ref "C87") (pin "1") (pinfunction "1_1") (pintype "passive"))
      (node (ref "C88") (pin "1") (pinfunction "1_1") (pintype "passive"))
      (node (ref "C89") (pin "1") (pinfunction "1_1") (pintype "passive"))
      (node (ref "C90") (pin "1") (pinfunction "1_1") (pintype "passive"))
      (node (ref "C91") (pin "1") (pinfunction "1_1") (pintype "passive"))
      (node (ref "C92") (pin "1") (pinfunction "1_1") (pintype "passive"))
      (node (ref "C93") (pin "1") (pinfunction "1_1") (pintype "passive"))
      (node (ref "C94") (pin "1") (pinfunction "1_1") (pintype "passive"))
      (node (ref "C95") (pin "1") (pinfunction "1_1") (pintype "passive"))
      (node (ref "C96") (pin "1") (pinfunction "1_1") (pintype "passive"))
      (node (ref "C97") (pin "1") (pinfunction "1_1") (pintype "passive"))
      (node (ref "C98") (pin "1") (pinfunction "1_1") (pintype "passive"))
      (node (ref "C99") (pin "1") (pinfunction "1_1") (pintype "passive"))
      (node (ref "IC10") (pin "1") (pinfunction "GND_1") (pintype "power_in"))
      (node (ref "IC10") (pin "17") (pinfunction "GND_17") (pintype "power_in"))
      (node (ref "IC10") (pin "18") (pinfunction "GND_18") (pintype "power_in"))
      (node (ref "IC10") (pin "2") (pinfunction "GND_2") (pintype "power_in"))
      (node (ref "IC10") (pin "33") (pinfunction "PAD(GND)_33") (pintype "power_in"))
      (node (ref "IC10") (pin "5") (pinfunction "GND_5") (pintype "power_in"))
      (node (ref "IC11") (pin "1") (pinfunction "GND_1") (pintype "power_in"))
      (node (ref "IC11") (pin "17") (pinfunction "GND_17") (pintype "power_in"))
      (node (ref "IC11") (pin "18") (pinfunction "GND_18") (pintype "power_in"))
      (node (ref "IC11") (pin "2") (pinfunction "GND_2") (pintype "power_in"))
      (node (ref "IC11") (pin "33") (pinfunction "PAD(GND)_33") (pintype "power_in"))
      (node (ref "IC11") (pin "5") (pinfunction "GND_5") (pintype "power_in"))
      (node (ref "IC12") (pin "1") (pinfunction "GND_1") (pintype "power_in"))
      (node (ref "IC12") (pin "17") (pinfunction "GND_17") (pintype "power_in"))
      (node (ref "IC12") (pin "18") (pinfunction "GND_18") (pintype "power_in"))
      (node (ref "IC12") (pin "2") (pinfunction "GND_2") (pintype "power_in"))
      (node (ref "IC12") (pin "33") (pinfunction "PAD(GND)_33") (pintype "power_in"))
      (node (ref "IC12") (pin "5") (pinfunction "GND_5") (pintype "power_in"))
      (node (ref "IC13") (pin "1") (pinfunction "GND_1") (pintype "power_in"))
      (node (ref "IC13") (pin "17") (pinfunction "GND_17") (pintype "power_in"))
      (node (ref "IC13") (pin "18") (pinfunction "GND_18") (pintype "power_in"))
      (node (ref "IC13") (pin "2") (pinfunction "GND_2") (pintype "power_in"))
      (node (ref "IC13") (pin "33") (pinfunction "PAD(GND)_33") (pintype "power_in"))
      (node (ref "IC13") (pin "5") (pinfunction "GND_5") (pintype "power_in"))
      (node (ref "IC5") (pin "1") (pinfunction "GND_1") (pintype "power_in"))
      (node (ref "IC5") (pin "17") (pinfunction "GND_17") (pintype "power_in"))
      (node (ref "IC5") (pin "18") (pinfunction "GND_18") (pintype "power_in"))
      (node (ref "IC5") (pin "2") (pinfunction "GND_2") (pintype "power_in"))
      (node (ref "IC5") (pin "33") (pinfunction "PAD(GND)_33") (pintype "power_in"))
      (node (ref "IC5") (pin "5") (pinfunction "GND_5") (pintype "power_in"))
      (node (ref "IC6") (pin "1") (pinfunction "GND_1") (pintype "power_in"))
      (node (ref "IC6") (pin "17") (pinfunction "GND_17") (pintype "power_in"))
      (node (ref "IC6") (pin "18") (pinfunction "GND_18") (pintype "power_in"))
      (node (ref "IC6") (pin "2") (pinfunction "GND_2") (pintype "power_in"))
      (node (ref "IC6") (pin "33") (pinfunction "PAD(GND)_33") (pintype "power_in"))
      (node (ref "IC6") (pin "5") (pinfunction "GND_5") (pintype "power_in"))
      (node (ref "IC7") (pin "1") (pinfunction "GND_1") (pintype "power_in"))
      (node (ref "IC7") (pin "17") (pinfunction "GND_17") (pintype "power_in"))
      (node (ref "IC7") (pin "18") (pinfunction "GND_18") (pintype "power_in"))
      (node (ref "IC7") (pin "2") (pinfunction "GND_2") (pintype "power_in"))
      (node (ref "IC7") (pin "33") (pinfunction "PAD(GND)_33") (pintype "power_in"))
      (node (ref "IC7") (pin "5") (pinfunction "GND_5") (pintype "power_in"))
      (node (ref "IC8") (pin "1") (pinfunction "GND_1") (pintype "power_in"))
      (node (ref "IC8") (pin "17") (pinfunction "GND_17") (pintype "power_in"))
      (node (ref "IC8") (pin "18") (pinfunction "GND_18") (pintype "power_in"))
      (node (ref "IC8") (pin "2") (pinfunction "GND_2") (pintype "power_in"))
      (node (ref "IC8") (pin "33") (pinfunction "PAD(GND)_33") (pintype "power_in"))
      (node (ref "IC8") (pin "5") (pinfunction "GND_5") (pintype "power_in"))
      (node (ref "IC9") (pin "1") (pinfunction "GND_1") (pintype "power_in"))
      (node (ref "IC9") (pin "17") (pinfunction "GND_17") (pintype "power_in"))
      (node (ref "IC9") (pin "18") (pinfunction "GND_18") (pintype "power_in"))
      (node (ref "IC9") (pin "2") (pinfunction "GND_2") (pintype "power_in"))
      (node (ref "IC9") (pin "33") (pinfunction "PAD(GND)_33") (pintype "power_in"))
      (node (ref "IC9") (pin "5") (pinfunction "GND_5") (pintype "power_in"))
    )
    (net (code "148") (name "P3V3_BUF") (class "Default")
      (node (ref "C100") (pin "2") (pinfunction "2_2") (pintype "passive"))
      (node (ref "C101") (pin "2") (pinfunction "2_2") (pintype "passive"))
      (node (ref "C102") (pin "2") (pinfunction "2_2") (pintype "passive"))
      (node (ref "C103") (pin "2") (pinfunction "2_2") (pintype "passive"))
      (node (ref "C104") (pin "2") (pinfunction "2_2") (pintype "passive"))
      (node (ref "C105") (pin "2") (pinfunction "2_2") (pintype "passive"))
      (node (ref "C106") (pin "2") (pinfunction "2_2") (pintype "passive"))
      (node (ref "C107") (pin "2") (pinfunction "2_2") (pintype "passive"))
      (node (ref "C108") (pin "2") (pinfunction "2_2") (pintype "passive"))
      (node (ref "C109") (pin "2") (pinfunction "2_2") (pintype "passive"))
      (node (ref "C110") (pin "2") (pinfunction "2_2") (pintype "passive"))
      (node (ref "C111") (pin "2") (pinfunction "2_2") (pintype "passive"))
      (node (ref "C112") (pin "2") (pinfunction "2_2") (pintype "passive"))
      (node (ref "C113") (pin "2") (pinfunction "2_2") (pintype "passive"))
      (node (ref "C114") (pin "2") (pinfunction "2_2") (pintype "passive"))
      (node (ref "C115") (pin "2") (pinfunction "2_2") (pintype "passive"))
      (node (ref "C116") (pin "2") (pinfunction "2_2") (pintype "passive"))
      (node (ref "C117") (pin "2") (pinfunction "2_2") (pintype "passive"))
      (node (ref "C118") (pin "2") (pinfunction "2_2") (pintype "passive"))
      (node (ref "C119") (pin "2") (pinfunction "2_2") (pintype "passive"))
      (node (ref "C120") (pin "2") (pinfunction "2_2") (pintype "passive"))
      (node (ref "C121") (pin "2") (pinfunction "2_2") (pintype "passive"))
      (node (ref "C122") (pin "2") (pinfunction "2_2") (pintype "passive"))
      (node (ref "C78") (pin "2") (pinfunction "2_2") (pintype "passive"))
      (node (ref "C79") (pin "2") (pinfunction "2_2") (pintype "passive"))
      (node (ref "C80") (pin "2") (pinfunction "2_2") (pintype "passive"))
      (node (ref "C81") (pin "2") (pinfunction "2_2") (pintype "passive"))
      (node (ref "C82") (pin "2") (pinfunction "2_2") (pintype "passive"))
      (node (ref "C83") (pin "2") (pinfunction "2_2") (pintype "passive"))
      (node (ref "C84") (pin "2") (pinfunction "2_2") (pintype "passive"))
      (node (ref "C85") (pin "2") (pinfunction "2_2") (pintype "passive"))
      (node (ref "C86") (pin "2") (pinfunction "2_2") (pintype "passive"))
      (node (ref "C87") (pin "2") (pinfunction "2_2") (pintype "passive"))
      (node (ref "C88") (pin "2") (pinfunction "2_2") (pintype "passive"))
      (node (ref "C89") (pin "2") (pinfunction "2_2") (pintype "passive"))
      (node (ref "C90") (pin "2") (pinfunction "2_2") (pintype "passive"))
      (node (ref "C91") (pin "2") (pinfunction "2_2") (pintype "passive"))
      (node (ref "C92") (pin "2") (pinfunction "2_2") (pintype "passive"))
      (node (ref "C93") (pin "2") (pinfunction "2_2") (pintype "passive"))
      (node (ref "C94") (pin "2") (pinfunction "2_2") (pintype "passive"))
      (node (ref "C95") (pin "2") (pinfunction "2_2") (pintype "passive"))
      (node (ref "C96") (pin "2") (pinfunction "2_2") (pintype "passive"))
      (node (ref "C97") (pin "2") (pinfunction "2_2") (pintype "passive"))
      (node (ref "C98") (pin "2") (pinfunction "2_2") (pintype "passive"))
      (node (ref "C99") (pin "2") (pinfunction "2_2") (pintype "passive"))
      (node (ref "IC10") (pin "19") (pinfunction "Vdd_19") (pintype "power_in"))
      (node (ref "IC10") (pin "20") (pinfunction "Vdd_20") (pintype "power_in"))
      (node (ref "IC10") (pin "21") (pinfunction "Vdd_21") (pintype "power_in"))
      (node (ref "IC10") (pin "22") (pinfunction "Vdd_22") (pintype "power_in"))
      (node (ref "IC10") (pin "3") (pinfunction "Vdd_3") (pintype "power_in"))
      (node (ref "IC10") (pin "4") (pinfunction "Vdd_4") (pintype "power_in"))
      (node (ref "IC10") (pin "6") (pinfunction "Vdd_6") (pintype "power_in"))
      (node (ref "IC10") (pin "7") (pinfunction "Vdd_7") (pintype "power_in"))
      (node (ref "IC10") (pin "8") (pinfunction "EN_8") (pintype "input"))
      (node (ref "IC11") (pin "19") (pinfunction "Vdd_19") (pintype "power_in"))
      (node (ref "IC11") (pin "20") (pinfunction "Vdd_20") (pintype "power_in"))
      (node (ref "IC11") (pin "21") (pinfunction "Vdd_21") (pintype "power_in"))
      (node (ref "IC11") (pin "22") (pinfunction "Vdd_22") (pintype "power_in"))
      (node (ref "IC11") (pin "3") (pinfunction "Vdd_3") (pintype "power_in"))
      (node (ref "IC11") (pin "4") (pinfunction "Vdd_4") (pintype "power_in"))
      (node (ref "IC11") (pin "6") (pinfunction "Vdd_6") (pintype "power_in"))
      (node (ref "IC11") (pin "7") (pinfunction "Vdd_7") (pintype "power_in"))
      (node (ref "IC11") (pin "8") (pinfunction "EN_8") (pintype "input"))
      (node (ref "IC12") (pin "19") (pinfunction "Vdd_19") (pintype "power_in"))
      (node (ref "IC12") (pin "20") (pinfunction "Vdd_20") (pintype "power_in"))
      (node (ref "IC12") (pin "21") (pinfunction "Vdd_21") (pintype "power_in"))
      (node (ref "IC12") (pin "22") (pinfunction "Vdd_22") (pintype "power_in"))
      (node (ref "IC12") (pin "3") (pinfunction "Vdd_3") (pintype "power_in"))
      (node (ref "IC12") (pin "4") (pinfunction "Vdd_4") (pintype "power_in"))
      (node (ref "IC12") (pin "6") (pinfunction "Vdd_6") (pintype "power_in"))
      (node (ref "IC12") (pin "7") (pinfunction "Vdd_7") (pintype "power_in"))
      (node (ref "IC12") (pin "8") (pinfunction "EN_8") (pintype "input"))
      (node (ref "IC13") (pin "19") (pinfunction "Vdd_19") (pintype "power_in"))
      (node (ref "IC13") (pin "20") (pinfunction "Vdd_20") (pintype "power_in"))
      (node (ref "IC13") (pin "21") (pinfunction "Vdd_21") (pintype "power_in"))
      (node (ref "IC13") (pin "22") (pinfunction "Vdd_22") (pintype "power_in"))
      (node (ref "IC13") (pin "3") (pinfunction "Vdd_3") (pintype "power_in"))
      (node (ref "IC13") (pin "4") (pinfunction "Vdd_4") (pintype "power_in"))
      (node (ref "IC13") (pin "6") (pinfunction "Vdd_6") (pintype "power_in"))
      (node (ref "IC13") (pin "7") (pinfunction "Vdd_7") (pintype "power_in"))
      (node (ref "IC13") (pin "8") (pinfunction "EN_8") (pintype "input"))
      (node (ref "IC5") (pin "19") (pinfunction "Vdd_19") (pintype "power_in"))
      (node (ref "IC5") (pin "20") (pinfunction "Vdd_20") (pintype "power_in"))
      (node (ref "IC5") (pin "21") (pinfunction "Vdd_21") (pintype "power_in"))
      (node (ref "IC5") (pin "22") (pinfunction "Vdd_22") (pintype "power_in"))
      (node (ref "IC5") (pin "3") (pinfunction "Vdd_3") (pintype "power_in"))
      (node (ref "IC5") (pin "4") (pinfunction "Vdd_4") (pintype "power_in"))
      (node (ref "IC5") (pin "6") (pinfunction "Vdd_6") (pintype "power_in"))
      (node (ref "IC5") (pin "7") (pinfunction "Vdd_7") (pintype "power_in"))
      (node (ref "IC5") (pin "8") (pinfunction "EN_8") (pintype "input"))
      (node (ref "IC6") (pin "19") (pinfunction "Vdd_19") (pintype "power_in"))
      (node (ref "IC6") (pin "20") (pinfunction "Vdd_20") (pintype "power_in"))
      (node (ref "IC6") (pin "21") (pinfunction "Vdd_21") (pintype "power_in"))
      (node (ref "IC6") (pin "22") (pinfunction "Vdd_22") (pintype "power_in"))
      (node (ref "IC6") (pin "3") (pinfunction "Vdd_3") (pintype "power_in"))
      (node (ref "IC6") (pin "4") (pinfunction "Vdd_4") (pintype "power_in"))
      (node (ref "IC6") (pin "6") (pinfunction "Vdd_6") (pintype "power_in"))
      (node (ref "IC6") (pin "7") (pinfunction "Vdd_7") (pintype "power_in"))
      (node (ref "IC6") (pin "8") (pinfunction "EN_8") (pintype "input"))
      (node (ref "IC7") (pin "19") (pinfunction "Vdd_19") (pintype "power_in"))
      (node (ref "IC7") (pin "20") (pinfunction "Vdd_20") (pintype "power_in"))
      (node (ref "IC7") (pin "21") (pinfunction "Vdd_21") (pintype "power_in"))
      (node (ref "IC7") (pin "22") (pinfunction "Vdd_22") (pintype "power_in"))
      (node (ref "IC7") (pin "3") (pinfunction "Vdd_3") (pintype "power_in"))
      (node (ref "IC7") (pin "4") (pinfunction "Vdd_4") (pintype "power_in"))
      (node (ref "IC7") (pin "6") (pinfunction "Vdd_6") (pintype "power_in"))
      (node (ref "IC7") (pin "7") (pinfunction "Vdd_7") (pintype "power_in"))
      (node (ref "IC7") (pin "8") (pinfunction "EN_8") (pintype "input"))
      (node (ref "IC8") (pin "19") (pinfunction "Vdd_19") (pintype "power_in"))
      (node (ref "IC8") (pin "20") (pinfunction "Vdd_20") (pintype "power_in"))
      (node (ref "IC8") (pin "21") (pinfunction "Vdd_21") (pintype "power_in"))
      (node (ref "IC8") (pin "22") (pinfunction "Vdd_22") (pintype "power_in"))
      (node (ref "IC8") (pin "3") (pinfunction "Vdd_3") (pintype "power_in"))
      (node (ref "IC8") (pin "4") (pinfunction "Vdd_4") (pintype "power_in"))
      (node (ref "IC8") (pin "6") (pinfunction "Vdd_6") (pintype "power_in"))
      (node (ref "IC8") (pin "7") (pinfunction "Vdd_7") (pintype "power_in"))
      (node (ref "IC8") (pin "8") (pinfunction "EN_8") (pintype "input"))
      (node (ref "IC9") (pin "19") (pinfunction "Vdd_19") (pintype "power_in"))
      (node (ref "IC9") (pin "20") (pinfunction "Vdd_20") (pintype "power_in"))
      (node (ref "IC9") (pin "21") (pinfunction "Vdd_21") (pintype "power_in"))
      (node (ref "IC9") (pin "22") (pinfunction "Vdd_22") (pintype "power_in"))
      (node (ref "IC9") (pin "3") (pinfunction "Vdd_3") (pintype "power_in"))
      (node (ref "IC9") (pin "4") (pinfunction "Vdd_4") (pintype "power_in"))
      (node (ref "IC9") (pin "6") (pinfunction "Vdd_6") (pintype "power_in"))
      (node (ref "IC9") (pin "7") (pinfunction "Vdd_7") (pintype "power_in"))
      (node (ref "IC9") (pin "8") (pinfunction "EN_8") (pintype "input"))
    )
    (net (code "149") (name "unconnected-(IC5-nc-Pad23)") (class "Default")
      (node (ref "IC5") (pin "23") (pinfunction "nc_23") (pintype "passive"))
    )
    (net (code "150") (name "unconnected-(IC5-nc-Pad24)") (class "Default")
      (node (ref "IC5") (pin "24") (pinfunction "nc_24") (pintype "passive"))
    )
    (net (code "151") (name "unconnected-(IC6-nc-Pad23)") (class "Default")
      (node (ref "IC6") (pin "23") (pinfunction "nc_23") (pintype "passive"))
    )
    (net (code "152") (name "unconnected-(IC6-nc-Pad24)") (class "Default")
      (node (ref "IC6") (pin "24") (pinfunction "nc_24") (pintype "passive"))
    )
    (net (code "153") (name "unconnected-(IC7-nc-Pad23)") (class "Default")
      (node (ref "IC7") (pin "23") (pinfunction "nc_23") (pintype "passive"))
    )
    (net (code "154") (name "unconnected-(IC7-nc-Pad24)") (class "Default")
      (node (ref "IC7") (pin "24") (pinfunction "nc_24") (pintype "passive"))
    )
    (net (code "155") (name "unconnected-(IC8-nc-Pad23)") (class "Default")
      (node (ref "IC8") (pin "23") (pinfunction "nc_23") (pintype "passive"))
    )
    (net (code "156") (name "unconnected-(IC8-nc-Pad24)") (class "Default")
      (node (ref "IC8") (pin "24") (pinfunction "nc_24") (pintype "passive"))
    )
    (net (code "157") (name "unconnected-(IC9-nc-Pad23)") (class "Default")
      (node (ref "IC9") (pin "23") (pinfunction "nc_23") (pintype "passive"))
    )
    (net (code "158") (name "unconnected-(IC9-nc-Pad24)") (class "Default")
      (node (ref "IC9") (pin "24") (pinfunction "nc_24") (pintype "passive"))
    )
    (net (code "159") (name "unconnected-(IC10-nc-Pad23)") (class "Default")
      (node (ref "IC10") (pin "23") (pinfunction "nc_23") (pintype "passive"))
    )
    (net (code "160") (name "unconnected-(IC10-nc-Pad24)") (class "Default")
      (node (ref "IC10") (pin "24") (pinfunction "nc_24") (pintype "passive"))
    )
    (net (code "161") (name "unconnected-(IC11-nc-Pad23)") (class "Default")
      (node (ref "IC11") (pin "23") (pinfunction "nc_23") (pintype "passive"))
    )
    (net (code "162") (name "unconnected-(IC11-nc-Pad24)") (class "Default")
      (node (ref "IC11") (pin "24") (pinfunction "nc_24") (pintype "passive"))
    )
    (net (code "163") (name "unconnected-(IC12-nc-Pad23)") (class "Default")
      (node (ref "IC12") (pin "23") (pinfunction "nc_23") (pintype "passive"))
    )
    (net (code "164") (name "unconnected-(IC12-nc-Pad24)") (class "Default")
      (node (ref "IC12") (pin "24") (pinfunction "nc_24") (pintype "passive"))
    )
    (net (code "165") (name "unconnected-(IC13-nc-Pad23)") (class "Default")
      (node (ref "IC13") (pin "23") (pinfunction "nc_23") (pintype "passive"))
    )
    (net (code "166") (name "unconnected-(IC13-nc-Pad24)") (class "Default")
      (node (ref "IC13") (pin "24") (pinfunction "nc_24") (pintype "passive"))
    )
  )
)
